# OpAmp.net
KiCad netlist of a schematic drawn in Altium Designer
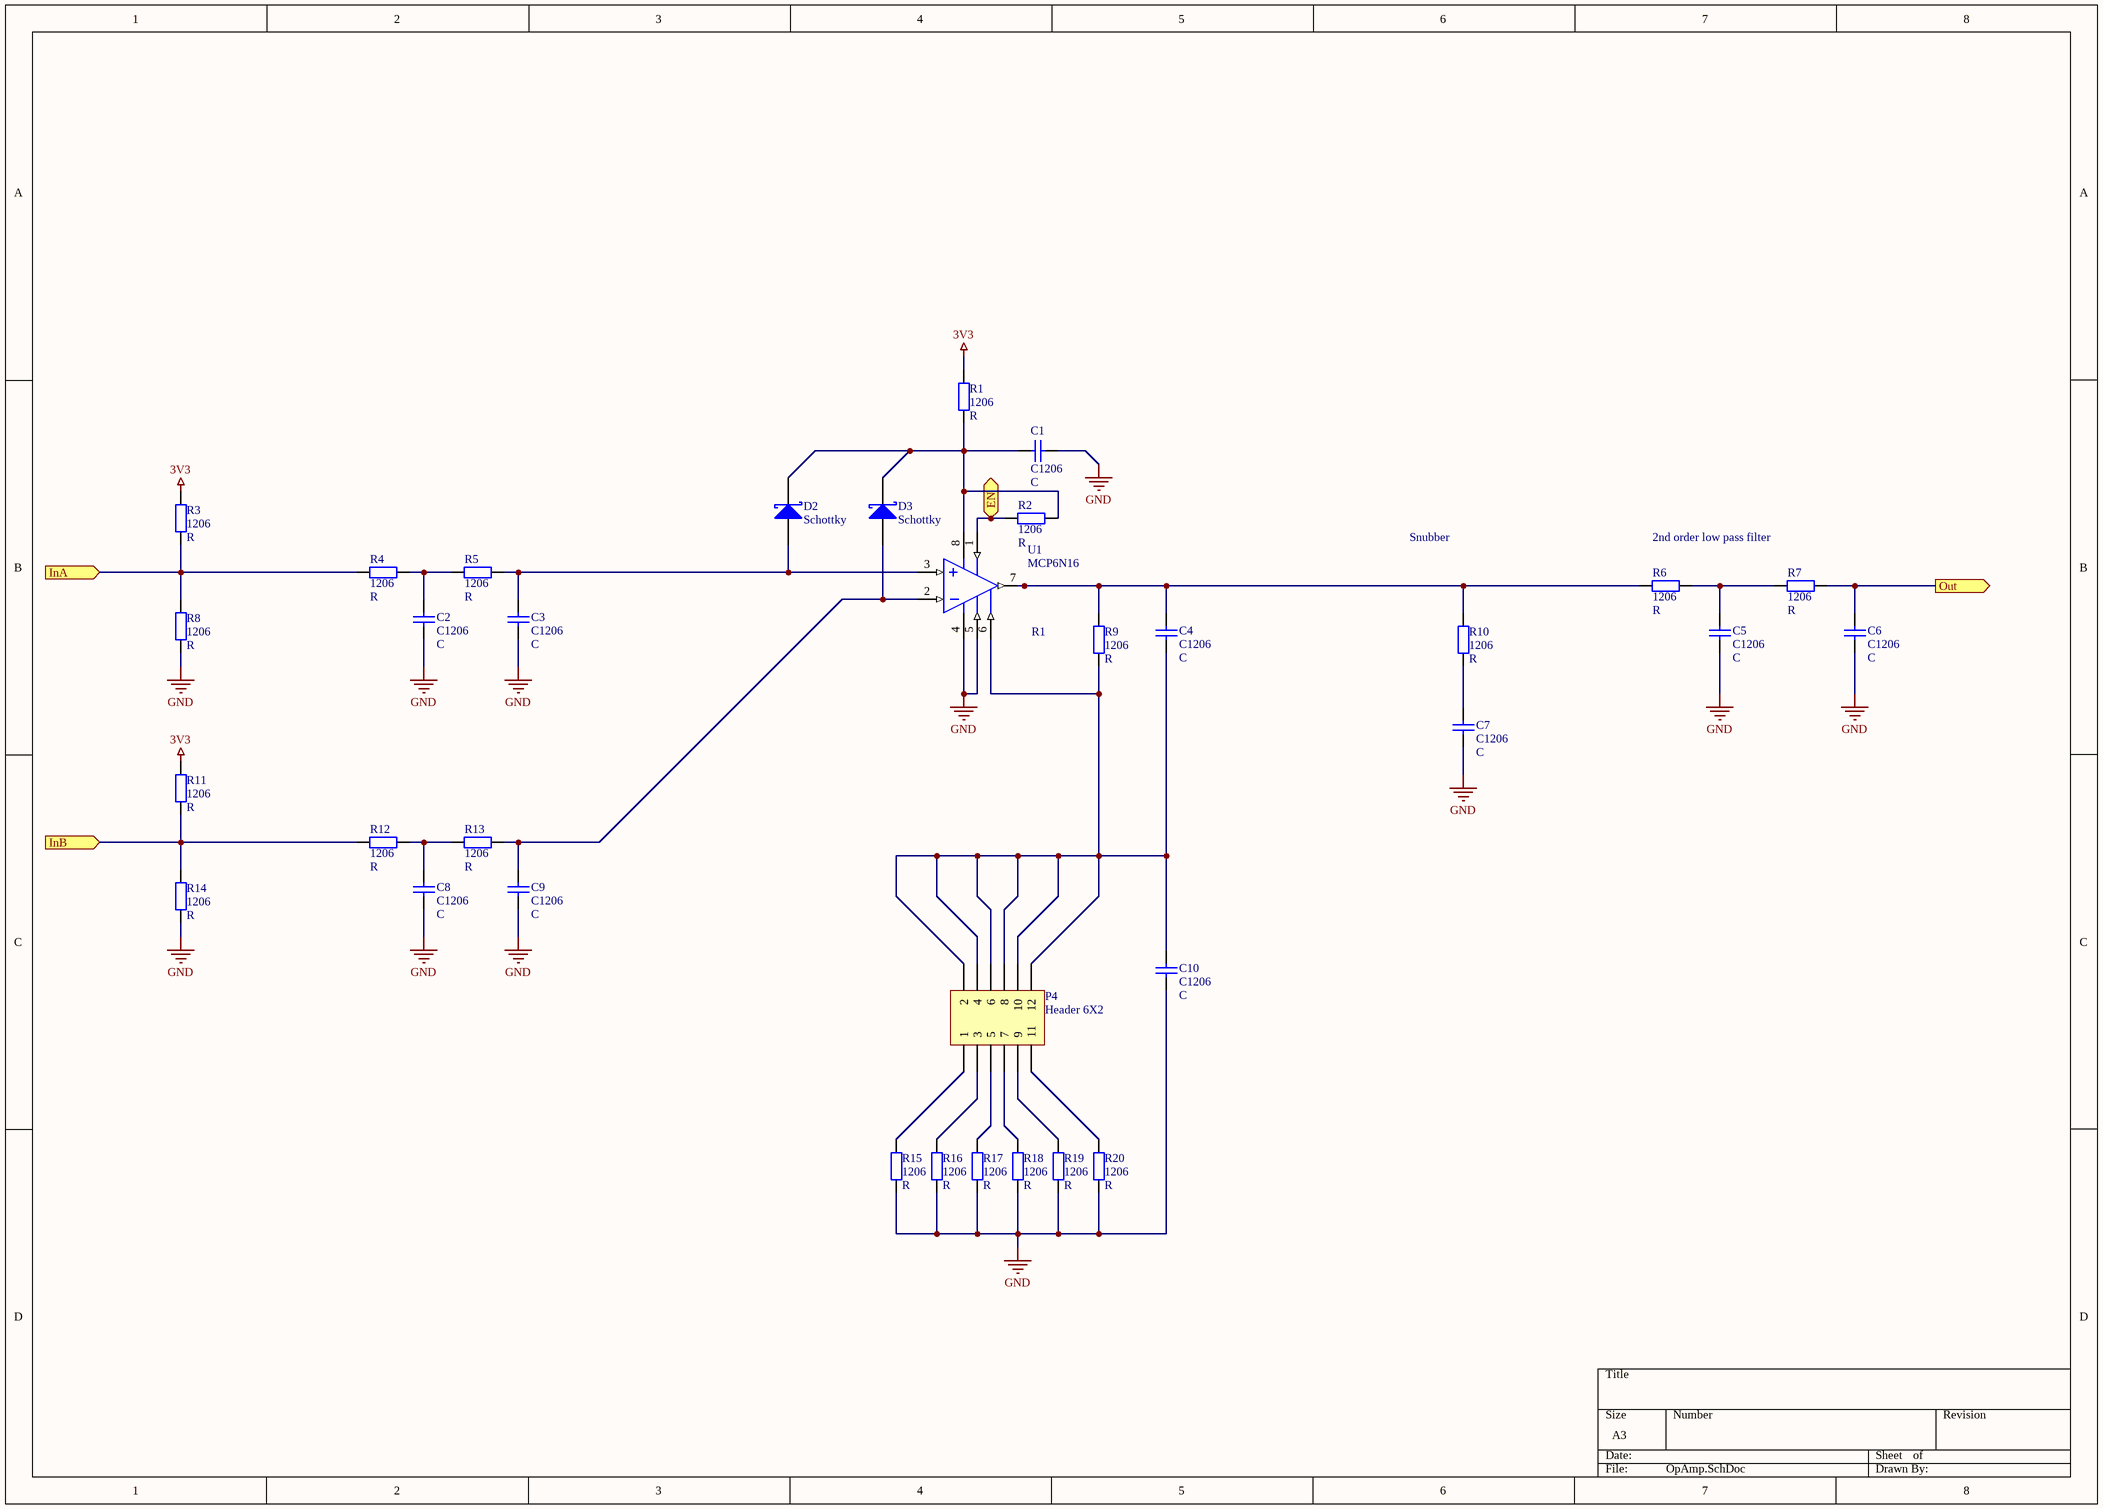
[diagram p0: OpAmp.SchDoc]

(export (version "E")
  (design (tool "Eeschema 10.0.6"))
  (components
    (comp (ref "C1")
      (value "C")
      (footprint "C1206")
      (description "Generic capacitor")
      (libsource (lib "RLC") (part "Cap"))
    )
    (comp (ref "C2")
      (value "C")
      (footprint "C1206")
      (description "Generic capacitor")
      (libsource (lib "RLC") (part "Cap"))
    )
    (comp (ref "C3")
      (value "C")
      (footprint "C1206")
      (description "Generic capacitor")
      (libsource (lib "RLC") (part "Cap"))
    )
    (comp (ref "C4")
      (value "C")
      (footprint "C1206")
      (description "Generic capacitor")
      (libsource (lib "RLC") (part "Cap"))
    )
    (comp (ref "C5")
      (value "C")
      (footprint "C1206")
      (description "Generic capacitor")
      (libsource (lib "RLC") (part "Cap"))
    )
    (comp (ref "C6")
      (value "C")
      (footprint "C1206")
      (description "Generic capacitor")
      (libsource (lib "RLC") (part "Cap"))
    )
    (comp (ref "C7")
      (value "C")
      (footprint "C1206")
      (description "Generic capacitor")
      (libsource (lib "RLC") (part "Cap"))
    )
    (comp (ref "C8")
      (value "C")
      (footprint "C1206")
      (description "Generic capacitor")
      (libsource (lib "RLC") (part "Cap"))
    )
    (comp (ref "C9")
      (value "C")
      (footprint "C1206")
      (description "Generic capacitor")
      (libsource (lib "RLC") (part "Cap"))
    )
    (comp (ref "C10")
      (value "C")
      (footprint "C1206")
      (description "Generic capacitor")
      (libsource (lib "RLC") (part "Cap"))
    )
    (comp (ref "D2")
      (value "Schottky")
      (footprint "SOD-323")
      (description "Schottky Rectifier")
      (libsource (lib "_Diodes") (part "SchottkyX"))
    )
    (comp (ref "D3")
      (value "Schottky")
      (footprint "SOD-323")
      (description "Schottky Rectifier")
      (libsource (lib "_Diodes") (part "SchottkyX"))
    )
    (comp (ref "P4")
      (value "Header 6X2")
      (footprint "HEADER 2X6 Male")
      (description "Header, 6-Pin, Dual row")
      (fields (field (name "PUBLISHER") "Altium Limited"))
      (libsource (lib "_Connectors") (part "Header 6X2"))
    )
    (comp (ref "R1")
      (value "R")
      (footprint "1206")
      (description "Generic resistor")
      (libsource (lib "") (part "Res_2"))
    )
    (comp (ref "R2")
      (value "R")
      (footprint "1206")
      (description "Generic resistor")
      (libsource (lib "RLC") (part "Res"))
    )
    (comp (ref "R3")
      (value "R")
      (footprint "1206")
      (description "Generic resistor")
      (libsource (lib "") (part "Res_1"))
    )
    (comp (ref "R4")
      (value "R")
      (footprint "1206")
      (description "Generic resistor")
      (libsource (lib "RLC") (part "Res"))
    )
    (comp (ref "R5")
      (value "R")
      (footprint "1206")
      (description "Generic resistor")
      (libsource (lib "RLC") (part "Res"))
    )
    (comp (ref "R6")
      (value "R")
      (footprint "1206")
      (description "Generic resistor")
      (libsource (lib "RLC") (part "Res"))
    )
    (comp (ref "R7")
      (value "R")
      (footprint "1206")
      (description "Generic resistor")
      (libsource (lib "RLC") (part "Res"))
    )
    (comp (ref "R8")
      (value "R")
      (footprint "1206")
      (description "Generic resistor")
      (libsource (lib "") (part "Res_1"))
    )
    (comp (ref "R9")
      (value "R")
      (footprint "1206")
      (description "Generic resistor")
      (libsource (lib "") (part "Res_1"))
    )
    (comp (ref "R10")
      (value "R")
      (footprint "1206")
      (description "Generic resistor")
      (libsource (lib "") (part "Res_1"))
    )
    (comp (ref "R11")
      (value "R")
      (footprint "1206")
      (description "Generic resistor")
      (libsource (lib "") (part "Res_1"))
    )
    (comp (ref "R12")
      (value "R")
      (footprint "1206")
      (description "Generic resistor")
      (libsource (lib "RLC") (part "Res"))
    )
    (comp (ref "R13")
      (value "R")
      (footprint "1206")
      (description "Generic resistor")
      (libsource (lib "RLC") (part "Res"))
    )
    (comp (ref "R14")
      (value "R")
      (footprint "1206")
      (description "Generic resistor")
      (libsource (lib "") (part "Res_1"))
    )
    (comp (ref "R15")
      (value "R")
      (footprint "1206")
      (description "Generic resistor")
      (libsource (lib "") (part "Res_1"))
    )
    (comp (ref "R16")
      (value "R")
      (footprint "1206")
      (description "Generic resistor")
      (libsource (lib "") (part "Res_1"))
    )
    (comp (ref "R17")
      (value "R")
      (footprint "1206")
      (description "Generic resistor")
      (libsource (lib "") (part "Res_1"))
    )
    (comp (ref "R18")
      (value "R")
      (footprint "1206")
      (description "Generic resistor")
      (libsource (lib "") (part "Res_1"))
    )
    (comp (ref "R19")
      (value "R")
      (footprint "1206")
      (description "Generic resistor")
      (libsource (lib "") (part "Res_1"))
    )
    (comp (ref "R20")
      (value "R")
      (footprint "1206")
      (description "Generic resistor")
      (libsource (lib "") (part "Res_1"))
    )
    (comp (ref "U1")
      (value "MCP6N16")
      (footprint "MSOP-MS8_M")
      (libsource (lib "_Microcircuits") (part "MCP6N16"))
    )
  )
  (nets
    (net (code "1") (name "/EN") (class "Default")
      (node (ref "R2") (pin "1") (pinfunction "1_1") (pintype "passive"))
      (node (ref "U1") (pin "1") (pinfunction "EN_1") (pintype "input"))
    )
    (net (code "2") (name "/InA") (class "Default")
      (node (ref "R3") (pin "2") (pinfunction "2_2") (pintype "passive"))
      (node (ref "R4") (pin "1") (pinfunction "1_1") (pintype "passive"))
      (node (ref "R8") (pin "1") (pinfunction "1_1") (pintype "passive"))
    )
    (net (code "3") (name "/InB") (class "Default")
      (node (ref "R11") (pin "2") (pinfunction "2_2") (pintype "passive"))
      (node (ref "R12") (pin "1") (pinfunction "1_1") (pintype "passive"))
      (node (ref "R14") (pin "1") (pinfunction "1_1") (pintype "passive"))
    )
    (net (code "4") (name "/Out") (class "Default")
      (node (ref "C6") (pin "2") (pinfunction "2_2") (pintype "passive"))
      (node (ref "R7") (pin "2") (pinfunction "2_2") (pintype "passive"))
    )
    (net (code "5") (name "3V3") (class "Default")
      (node (ref "R1") (pin "2") (pinfunction "2_2") (pintype "passive"))
      (node (ref "R11") (pin "1") (pinfunction "1_1") (pintype "passive"))
      (node (ref "R3") (pin "1") (pinfunction "1_1") (pintype "passive"))
    )
    (net (code "6") (name "GND") (class "Default")
      (node (ref "C1") (pin "2") (pinfunction "2_2") (pintype "passive"))
      (node (ref "C10") (pin "1") (pinfunction "1_1") (pintype "passive"))
      (node (ref "C2") (pin "2") (pinfunction "2_2") (pintype "passive"))
      (node (ref "C3") (pin "2") (pinfunction "2_2") (pintype "passive"))
      (node (ref "C5") (pin "1") (pinfunction "1_1") (pintype "passive"))
      (node (ref "C6") (pin "1") (pinfunction "1_1") (pintype "passive"))
      (node (ref "C7") (pin "1") (pinfunction "1_1") (pintype "passive"))
      (node (ref "C8") (pin "2") (pinfunction "2_2") (pintype "passive"))
      (node (ref "C9") (pin "2") (pinfunction "2_2") (pintype "passive"))
      (node (ref "R14") (pin "2") (pinfunction "2_2") (pintype "passive"))
      (node (ref "R15") (pin "2") (pinfunction "2_2") (pintype "passive"))
      (node (ref "R16") (pin "2") (pinfunction "2_2") (pintype "passive"))
      (node (ref "R17") (pin "2") (pinfunction "2_2") (pintype "passive"))
      (node (ref "R18") (pin "2") (pinfunction "2_2") (pintype "passive"))
      (node (ref "R19") (pin "2") (pinfunction "2_2") (pintype "passive"))
      (node (ref "R20") (pin "2") (pinfunction "2_2") (pintype "passive"))
      (node (ref "R8") (pin "2") (pinfunction "2_2") (pintype "passive"))
      (node (ref "U1") (pin "4") (pinfunction "VSS_4") (pintype "power_in"))
      (node (ref "U1") (pin "5") (pinfunction "Vref_5") (pintype "input"))
    )
    (net (code "7") (name "Net-(C2-Pad1)") (class "Default")
      (node (ref "C2") (pin "1") (pinfunction "1_1") (pintype "passive"))
      (node (ref "R4") (pin "2") (pinfunction "2_2") (pintype "passive"))
      (node (ref "R5") (pin "1") (pinfunction "1_1") (pintype "passive"))
    )
    (net (code "8") (name "Net-(C5-Pad2)") (class "Default")
      (node (ref "C5") (pin "2") (pinfunction "2_2") (pintype "passive"))
      (node (ref "R6") (pin "2") (pinfunction "2_2") (pintype "passive"))
      (node (ref "R7") (pin "1") (pinfunction "1_1") (pintype "passive"))
    )
    (net (code "9") (name "Net-(C7-Pad2)") (class "Default")
      (node (ref "C7") (pin "2") (pinfunction "2_2") (pintype "passive"))
      (node (ref "R10") (pin "2") (pinfunction "2_2") (pintype "passive"))
    )
    (net (code "10") (name "Net-(C8-Pad1)") (class "Default")
      (node (ref "C8") (pin "1") (pinfunction "1_1") (pintype "passive"))
      (node (ref "R12") (pin "2") (pinfunction "2_2") (pintype "passive"))
      (node (ref "R13") (pin "1") (pinfunction "1_1") (pintype "passive"))
    )
    (net (code "11") (name "Net-(D2-A)") (class "Default")
      (node (ref "C3") (pin "1") (pinfunction "1_1") (pintype "passive"))
      (node (ref "D2") (pin "1") (pinfunction "A_1") (pintype "passive"))
      (node (ref "R5") (pin "2") (pinfunction "2_2") (pintype "passive"))
      (node (ref "U1") (pin "3") (pinfunction "VIN+_3") (pintype "input"))
    )
    (net (code "12") (name "Net-(D2-K)") (class "Default")
      (node (ref "C1") (pin "1") (pinfunction "1_1") (pintype "passive"))
      (node (ref "D2") (pin "2") (pinfunction "K_2") (pintype "passive"))
      (node (ref "D3") (pin "2") (pinfunction "K_2") (pintype "passive"))
      (node (ref "R1") (pin "1") (pinfunction "1_1") (pintype "passive"))
      (node (ref "R2") (pin "2") (pinfunction "2_2") (pintype "passive"))
      (node (ref "U1") (pin "8") (pinfunction "VDD_8") (pintype "power_in"))
    )
    (net (code "13") (name "Net-(D3-A)") (class "Default")
      (node (ref "C9") (pin "1") (pinfunction "1_1") (pintype "passive"))
      (node (ref "D3") (pin "1") (pinfunction "A_1") (pintype "passive"))
      (node (ref "R13") (pin "2") (pinfunction "2_2") (pintype "passive"))
      (node (ref "U1") (pin "2") (pinfunction "VIN-_2") (pintype "input"))
    )
    (net (code "14") (name "Net-(P4-Pad1)") (class "Default")
      (node (ref "P4") (pin "1") (pinfunction "1_1") (pintype "passive"))
      (node (ref "R15") (pin "1") (pinfunction "1_1") (pintype "passive"))
    )
    (net (code "15") (name "Net-(P4-Pad3)") (class "Default")
      (node (ref "P4") (pin "3") (pinfunction "3_3") (pintype "passive"))
      (node (ref "R16") (pin "1") (pinfunction "1_1") (pintype "passive"))
    )
    (net (code "16") (name "Net-(P4-Pad5)") (class "Default")
      (node (ref "P4") (pin "5") (pinfunction "5_5") (pintype "passive"))
      (node (ref "R17") (pin "1") (pinfunction "1_1") (pintype "passive"))
    )
    (net (code "17") (name "Net-(P4-Pad7)") (class "Default")
      (node (ref "P4") (pin "7") (pinfunction "7_7") (pintype "passive"))
      (node (ref "R18") (pin "1") (pinfunction "1_1") (pintype "passive"))
    )
    (net (code "18") (name "Net-(P4-Pad9)") (class "Default")
      (node (ref "P4") (pin "9") (pinfunction "9_9") (pintype "passive"))
      (node (ref "R19") (pin "1") (pinfunction "1_1") (pintype "passive"))
    )
    (net (code "19") (name "Net-(P4-Pad11)") (class "Default")
      (node (ref "P4") (pin "11") (pinfunction "11_11") (pintype "passive"))
      (node (ref "R20") (pin "1") (pinfunction "1_1") (pintype "passive"))
    )
    (net (code "20") (name "Net-(U1-FB)") (class "Default")
      (node (ref "C10") (pin "2") (pinfunction "2_2") (pintype "passive"))
      (node (ref "C4") (pin "1") (pinfunction "1_1") (pintype "passive"))
      (node (ref "P4") (pin "10") (pinfunction "10_10") (pintype "passive"))
      (node (ref "P4") (pin "12") (pinfunction "12_12") (pintype "passive"))
      (node (ref "P4") (pin "2") (pinfunction "2_2") (pintype "passive"))
      (node (ref "P4") (pin "4") (pinfunction "4_4") (pintype "passive"))
      (node (ref "P4") (pin "6") (pinfunction "6_6") (pintype "passive"))
      (node (ref "P4") (pin "8") (pinfunction "8_8") (pintype "passive"))
      (node (ref "R9") (pin "2") (pinfunction "2_2") (pintype "passive"))
      (node (ref "U1") (pin "6") (pinfunction "FB_6") (pintype "input"))
    )
    (net (code "21") (name "Net-(U1-VOUT)") (class "Default")
      (node (ref "C4") (pin "2") (pinfunction "2_2") (pintype "passive"))
      (node (ref "R10") (pin "1") (pinfunction "1_1") (pintype "passive"))
      (node (ref "R6") (pin "1") (pinfunction "1_1") (pintype "passive"))
      (node (ref "R9") (pin "1") (pinfunction "1_1") (pintype "passive"))
      (node (ref "U1") (pin "7") (pinfunction "VOUT_7") (pintype "output"))
    )
  )
)
